# SCH_keeley_4_knob_compressor_2022-01-26.net
KiCad netlist of a schematic drawn in EasyEDA
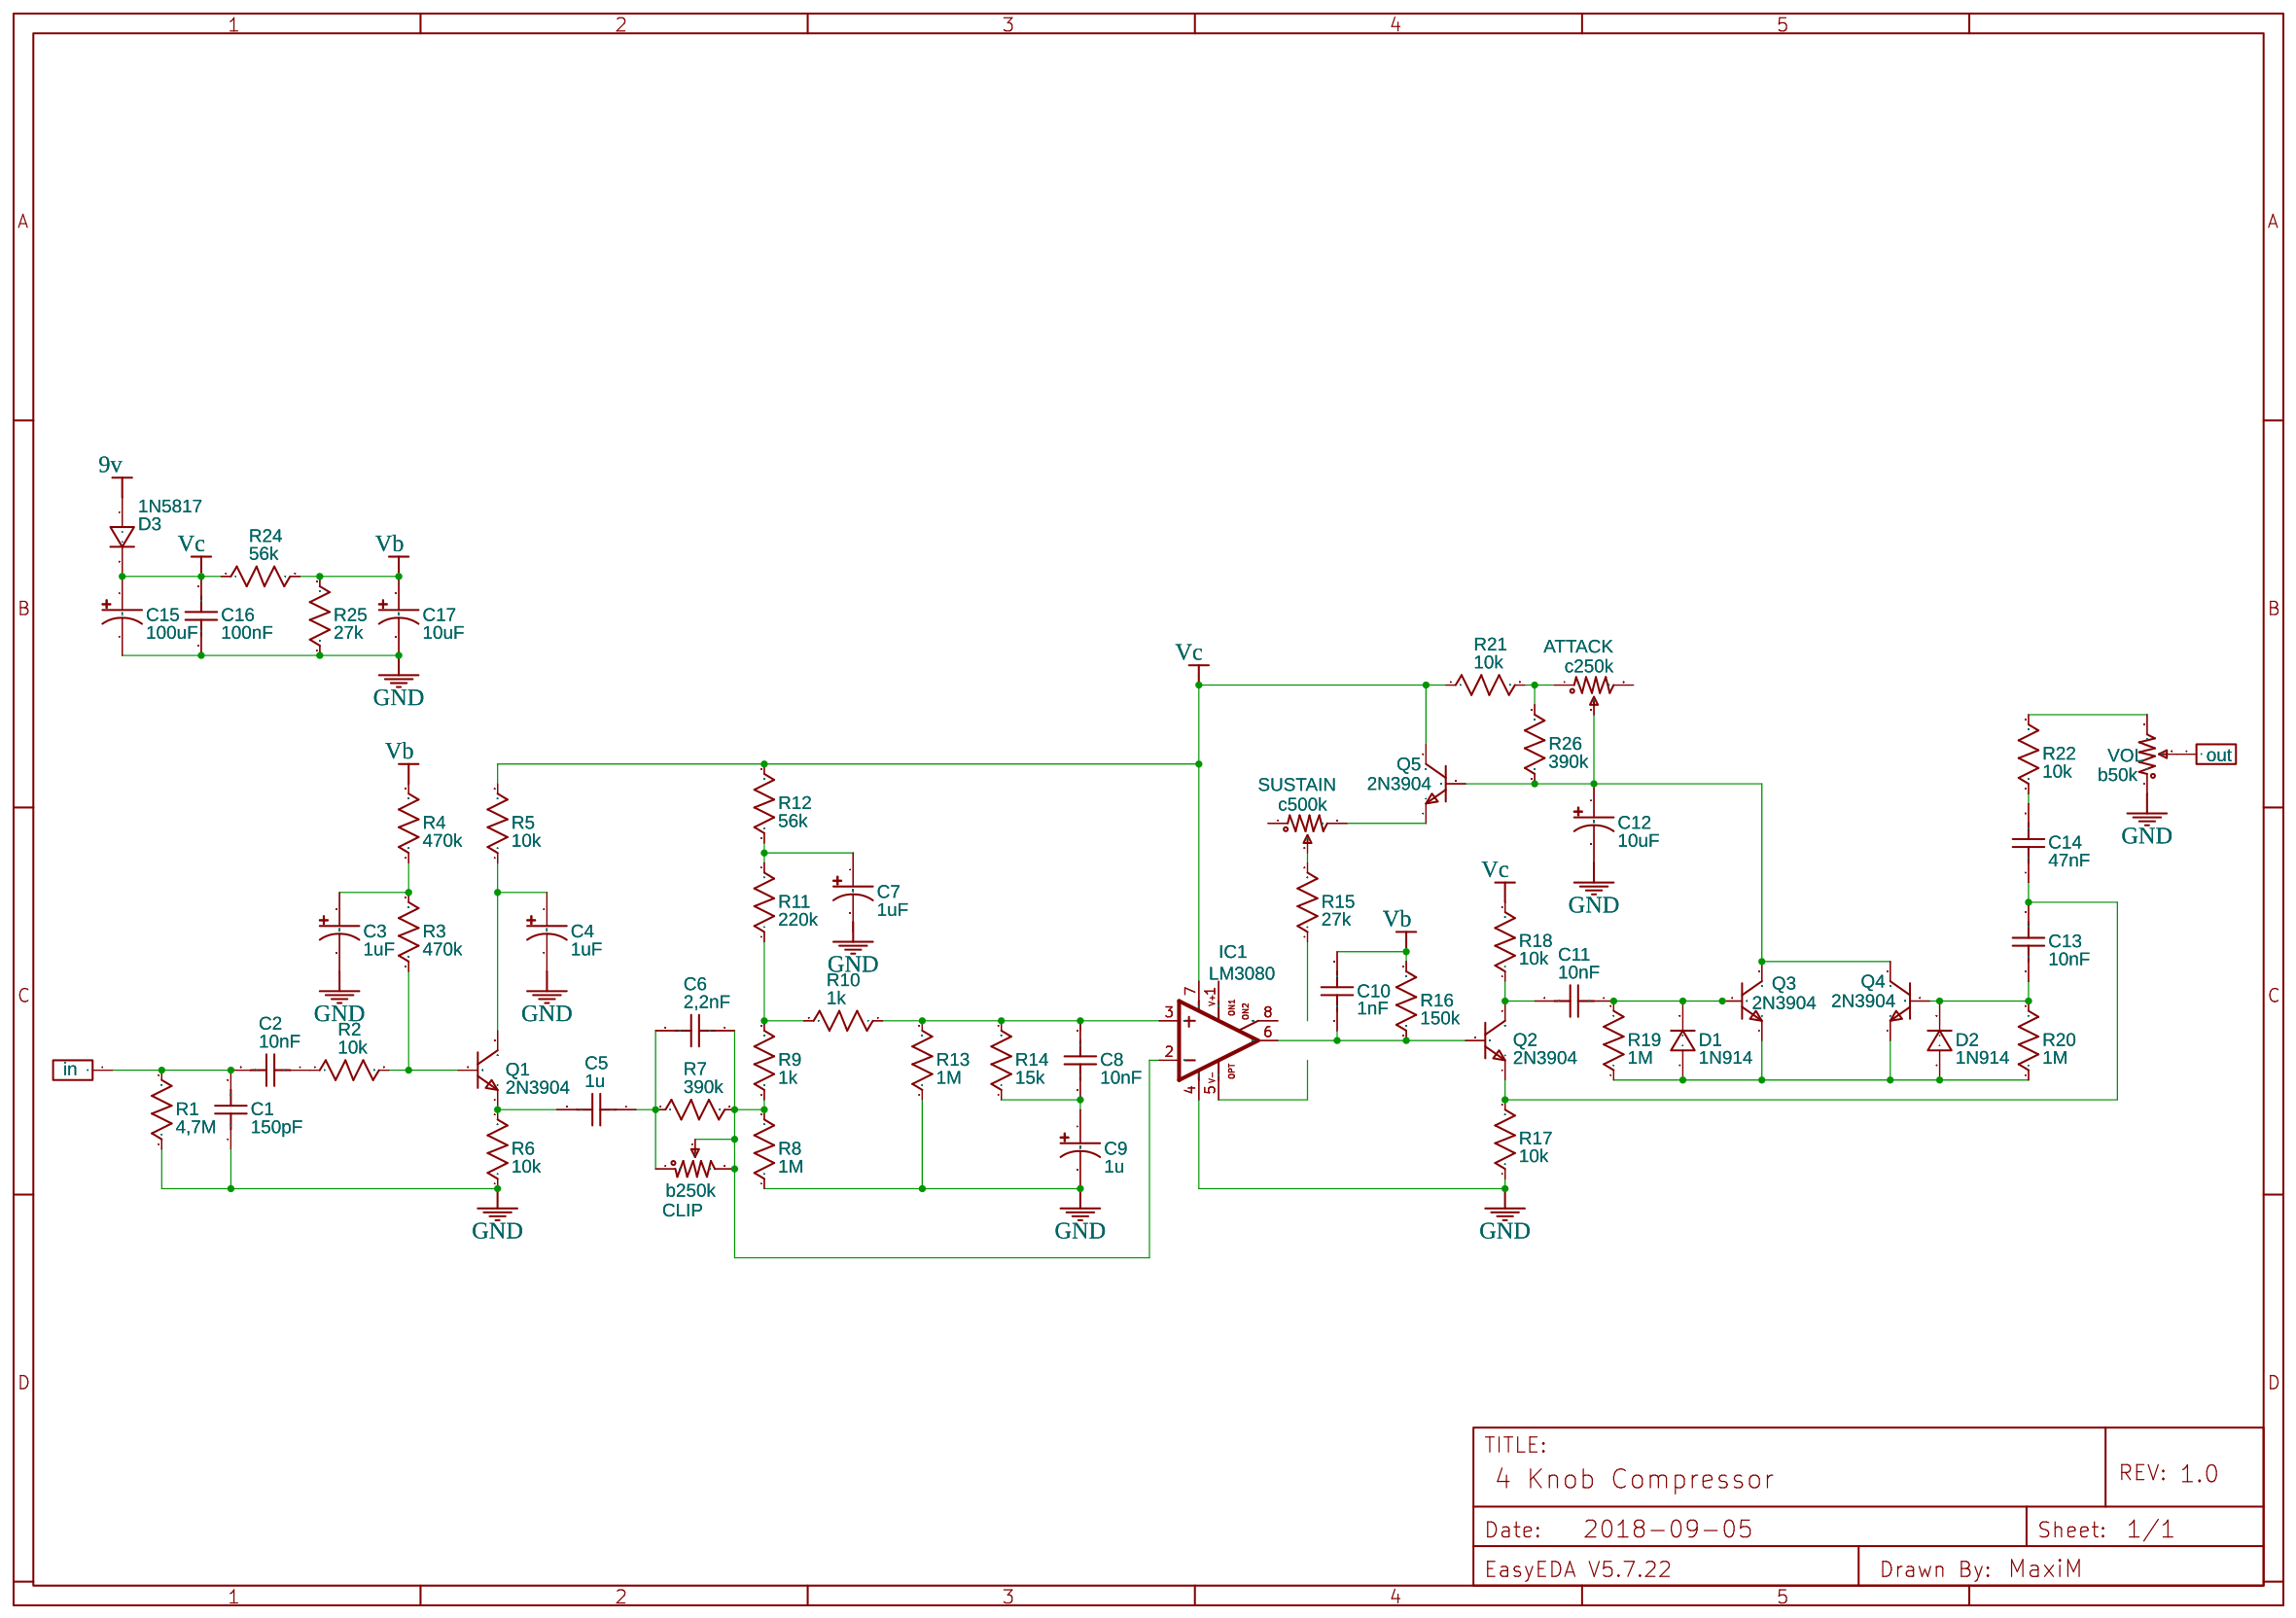
[diagram p0: schematic sheet]

(export (version "E")
  (design (tool "Eeschema 10.0.6"))
  (components
    (comp (ref "ATTACK")
      (value "c250k")
      (fields
        (field (name "BOM_Manufacturer Part") "3386P-1-101LF")
        (field (name "BOM_Supplier Part") "C125022")
      )
      (libsource (lib "") (part "3386P-1-101LF_US_2"))
    )
    (comp (ref "C1")
      (value "150pF")
      (fields (field (name "BOM_Manufacturer Part") "?"))
      (libsource (lib "") (part "Cap_RAD-0.1_US_1"))
    )
    (comp (ref "C2")
      (value "10nF")
      (fields (field (name "BOM_Manufacturer Part") "?"))
      (libsource (lib "") (part "Cap_RAD-0.1_US"))
    )
    (comp (ref "C3")
      (value "1uF")
      (fields (field (name "BOM_Manufacturer Part") "?"))
      (libsource (lib "") (part "Cap_Electrolytic(TH)_D3.0XF1.5_US_1"))
    )
    (comp (ref "C4")
      (value "1uF")
      (fields (field (name "BOM_Manufacturer Part") "?"))
      (libsource (lib "") (part "Cap_Electrolytic(TH)_D3.0XF1.5_US"))
    )
    (comp (ref "C5")
      (value "1u")
      (fields (field (name "BOM_Manufacturer Part") "?"))
      (libsource (lib "") (part "Cap_RAD-0.1_US"))
    )
    (comp (ref "C6")
      (value "2,2nF")
      (fields (field (name "BOM_Manufacturer Part") "?"))
      (libsource (lib "") (part "Cap_RAD-0.1_US"))
    )
    (comp (ref "C7")
      (value "1uF")
      (fields (field (name "BOM_Manufacturer Part") "?"))
      (libsource (lib "") (part "Cap_Electrolytic(TH)_D3.0XF1.5_US"))
    )
    (comp (ref "C8")
      (value "10nF")
      (fields (field (name "BOM_Manufacturer Part") "?"))
      (libsource (lib "") (part "Cap_RAD-0.1_US_1"))
    )
    (comp (ref "C9")
      (value "1u")
      (fields (field (name "BOM_Manufacturer Part") "?"))
      (libsource (lib "") (part "Cap_Electrolytic(TH)_D3.0XF1.5_US"))
    )
    (comp (ref "C10")
      (value "1nF")
      (fields (field (name "BOM_Manufacturer Part") "?"))
      (libsource (lib "") (part "Cap_RAD-0.1_US_1"))
    )
    (comp (ref "C11")
      (value "10nF")
      (fields (field (name "BOM_Manufacturer Part") "?"))
      (libsource (lib "") (part "Cap_RAD-0.1_US"))
    )
    (comp (ref "C12")
      (value "10uF")
      (fields (field (name "BOM_Manufacturer Part") "?"))
      (libsource (lib "") (part "Cap_Electrolytic(TH)_D3.0XF1.5_US"))
    )
    (comp (ref "C13")
      (value "10nF")
      (fields (field (name "BOM_Manufacturer Part") "?"))
      (libsource (lib "") (part "Cap_RAD-0.1_US_1"))
    )
    (comp (ref "C14")
      (value "47nF")
      (fields (field (name "BOM_Manufacturer Part") "?"))
      (libsource (lib "") (part "Cap_RAD-0.1_US_1"))
    )
    (comp (ref "C15")
      (value "100uF")
      (fields (field (name "BOM_Manufacturer Part") "?"))
      (libsource (lib "") (part "Cap_Electrolytic(TH)_D3.0XF1.5_US"))
    )
    (comp (ref "C16")
      (value "100nF")
      (fields (field (name "BOM_Manufacturer Part") "?"))
      (libsource (lib "") (part "Cap_RAD-0.1_US_1"))
    )
    (comp (ref "C17")
      (value "10uF")
      (fields (field (name "BOM_Manufacturer Part") "?"))
      (libsource (lib "") (part "Cap_Electrolytic(TH)_D3.0XF1.5_US_1"))
    )
    (comp (ref "CLIP")
      (value "b250k")
      (fields
        (field (name "BOM_Manufacturer Part") "3386P-1-101LF")
        (field (name "BOM_Supplier Part") "C125022")
      )
      (libsource (lib "") (part "3386P-1-101LF_US_3"))
    )
    (comp (ref "D1")
      (value "1N914")
      (fields (field (name "BOM_Manufacturer Part") "1N4448") (field (name "BOM_Supplier Part") "C54037"))
      (libsource (lib "") (part "Unknown_845_520"))
    )
    (comp (ref "D2")
      (value "1N914")
      (fields (field (name "BOM_Manufacturer Part") "1N4448") (field (name "BOM_Supplier Part") "C54037"))
      (libsource (lib "") (part "Unknown_975_520"))
    )
    (comp (ref "D3")
      (value "1N5817")
      (fields (field (name "BOM_Manufacturer Part") "1N4448") (field (name "BOM_Supplier Part") "C54037"))
      (libsource (lib "") (part "Unknown_55_265"))
    )
    (comp (ref "IC1")
      (value "LM3080")
      (fields (field (name "BOM_Manufacturer Part") "?"))
      (libsource (lib "") (part "Unknown_610_520"))
    )
    (comp (ref "P1")
      (value "in")
      (fields
        (field (name "BOM_Manufacturer Part") "Header-Male-2.54_1x1")
        (field (name "BOM_Supplier Part") "C81276")
      )
      (libsource (lib "") (part "Unknown_35_535"))
    )
    (comp (ref "P2")
      (value "out")
      (fields
        (field (name "BOM_Manufacturer Part") "Header-Male-2.54_1x1")
        (field (name "BOM_Supplier Part") "C81276")
      )
      (libsource (lib "") (part "Unknown_1110_375"))
    )
    (comp (ref "Q1")
      (value "2N3904")
      (fields (field (name "BOM_Supplier Part") "C118538"))
      (libsource (lib "") (part "Unknown_235_535"))
    )
    (comp (ref "Q2")
      (value "2N3904")
      (fields (field (name "BOM_Supplier Part") "C118538"))
      (libsource (lib "") (part "Unknown_745_520"))
    )
    (comp (ref "Q3")
      (value "2N3904")
      (fields (field (name "BOM_Supplier Part") "C118538"))
      (libsource (lib "") (part "Unknown_875_500"))
    )
    (comp (ref "Q4")
      (value "2N3904")
      (fields (field (name "BOM_Supplier Part") "C118538"))
      (libsource (lib "") (part "Unknown_960_500"))
    )
    (comp (ref "Q5")
      (value "2N3904")
      (fields (field (name "BOM_Supplier Part") "C118538"))
      (libsource (lib "") (part "Unknown_725_390"))
    )
    (comp (ref "R1")
      (value "4,7M")
      (fields (field (name "BOM_Manufacturer Part") "?"))
      (libsource (lib "") (part "Res_AXIAL-0.4(1/4W)_US"))
    )
    (comp (ref "R2")
      (value "10k")
      (fields (field (name "BOM_Manufacturer Part") "?"))
      (libsource (lib "") (part "Res_AXIAL-0.4(1/4W)_US_1"))
    )
    (comp (ref "R3")
      (value "470k")
      (fields (field (name "BOM_Manufacturer Part") "?"))
      (libsource (lib "") (part "Res_AXIAL-0.4(1/4W)_US"))
    )
    (comp (ref "R4")
      (value "470k")
      (fields (field (name "BOM_Manufacturer Part") "?"))
      (libsource (lib "") (part "Res_AXIAL-0.4(1/4W)_US"))
    )
    (comp (ref "R5")
      (value "10k")
      (fields (field (name "BOM_Manufacturer Part") "?"))
      (libsource (lib "") (part "Res_AXIAL-0.4(1/4W)_US"))
    )
    (comp (ref "R6")
      (value "10k")
      (fields (field (name "BOM_Manufacturer Part") "?"))
      (libsource (lib "") (part "Res_AXIAL-0.4(1/4W)_US"))
    )
    (comp (ref "R7")
      (value "390k")
      (fields (field (name "BOM_Manufacturer Part") "?"))
      (libsource (lib "") (part "Res_AXIAL-0.4(1/4W)_US_1"))
    )
    (comp (ref "R8")
      (value "1M")
      (fields (field (name "BOM_Manufacturer Part") "?"))
      (libsource (lib "") (part "Res_AXIAL-0.4(1/4W)_US"))
    )
    (comp (ref "R9")
      (value "1k")
      (fields (field (name "BOM_Manufacturer Part") "?"))
      (libsource (lib "") (part "Res_AXIAL-0.4(1/4W)_US"))
    )
    (comp (ref "R10")
      (value "1k")
      (fields (field (name "BOM_Manufacturer Part") "?"))
      (libsource (lib "") (part "Res_AXIAL-0.4(1/4W)_US_2"))
    )
    (comp (ref "R11")
      (value "220k")
      (fields (field (name "BOM_Manufacturer Part") "?"))
      (libsource (lib "") (part "Res_AXIAL-0.4(1/4W)_US"))
    )
    (comp (ref "R12")
      (value "56k")
      (fields (field (name "BOM_Manufacturer Part") "?"))
      (libsource (lib "") (part "Res_AXIAL-0.4(1/4W)_US"))
    )
    (comp (ref "R13")
      (value "1M")
      (fields (field (name "BOM_Manufacturer Part") "?"))
      (libsource (lib "") (part "Res_AXIAL-0.4(1/4W)_US"))
    )
    (comp (ref "R14")
      (value "15k")
      (fields (field (name "BOM_Manufacturer Part") "?"))
      (libsource (lib "") (part "Res_AXIAL-0.4(1/4W)_US"))
    )
    (comp (ref "R15")
      (value "27k")
      (fields (field (name "BOM_Manufacturer Part") "?"))
      (libsource (lib "") (part "Res_AXIAL-0.4(1/4W)_US"))
    )
    (comp (ref "R16")
      (value "150k")
      (fields (field (name "BOM_Manufacturer Part") "?"))
      (libsource (lib "") (part "Res_AXIAL-0.4(1/4W)_US"))
    )
    (comp (ref "R17")
      (value "10k")
      (fields (field (name "BOM_Manufacturer Part") "?"))
      (libsource (lib "") (part "Res_AXIAL-0.4(1/4W)_US"))
    )
    (comp (ref "R18")
      (value "10k")
      (fields (field (name "BOM_Manufacturer Part") "?"))
      (libsource (lib "") (part "Res_AXIAL-0.4(1/4W)_US"))
    )
    (comp (ref "R19")
      (value "1M")
      (fields (field (name "BOM_Manufacturer Part") "?"))
      (libsource (lib "") (part "Res_AXIAL-0.4(1/4W)_US"))
    )
    (comp (ref "R20")
      (value "1M")
      (fields (field (name "BOM_Manufacturer Part") "?"))
      (libsource (lib "") (part "Res_AXIAL-0.4(1/4W)_US"))
    )
    (comp (ref "R21")
      (value "10k")
      (fields (field (name "BOM_Manufacturer Part") "?"))
      (libsource (lib "") (part "Res_AXIAL-0.4(1/4W)_US_1"))
    )
    (comp (ref "R22")
      (value "10k")
      (fields (field (name "BOM_Manufacturer Part") "?"))
      (libsource (lib "") (part "Res_AXIAL-0.4(1/4W)_US"))
    )
    (comp (ref "R24")
      (value "56k")
      (fields (field (name "BOM_Manufacturer Part") "?"))
      (libsource (lib "") (part "Res_AXIAL-0.4(1/4W)_US_1"))
    )
    (comp (ref "R25")
      (value "27k")
      (fields (field (name "BOM_Manufacturer Part") "?"))
      (libsource (lib "") (part "Res_AXIAL-0.4(1/4W)_US"))
    )
    (comp (ref "R26")
      (value "390k")
      (fields (field (name "BOM_Manufacturer Part") "?"))
      (libsource (lib "") (part "Res_AXIAL-0.4(1/4W)_US"))
    )
    (comp (ref "SUSTAIN")
      (value "c500k")
      (fields
        (field (name "BOM_Manufacturer Part") "3386P-1-101LF")
        (field (name "BOM_Supplier Part") "C125022")
      )
      (libsource (lib "") (part "3386P-1-101LF_US"))
    )
    (comp (ref "VOL")
      (value "b50k")
      (fields
        (field (name "BOM_Manufacturer Part") "3386P-1-101LF")
        (field (name "BOM_Supplier Part") "C125022")
      )
      (libsource (lib "") (part "3386P-1-101LF_US_1"))
    )
  )
  (nets
    (net (code "1") (name "9v") (class "Default")
      (node (ref "D3") (pin "1") (pinfunction "A_1") (pintype "unspecified"))
    )
    (net (code "2") (name "GND") (class "Default")
      (node (ref "C1") (pin "1") (pinfunction "1_1") (pintype "unspecified"))
      (node (ref "C12") (pin "2") (pinfunction "2_2") (pintype "unspecified"))
      (node (ref "C15") (pin "2") (pinfunction "2_2") (pintype "unspecified"))
      (node (ref "C16") (pin "1") (pinfunction "1_1") (pintype "unspecified"))
      (node (ref "C17") (pin "2") (pinfunction "2_2") (pintype "unspecified"))
      (node (ref "C3") (pin "2") (pinfunction "2_2") (pintype "unspecified"))
      (node (ref "C4") (pin "2") (pinfunction "2_2") (pintype "unspecified"))
      (node (ref "C9") (pin "2") (pinfunction "2_2") (pintype "unspecified"))
      (node (ref "IC1") (pin "4") (pinfunction "V-_4") (pintype "passive"))
      (node (ref "R1") (pin "1") (pinfunction "1_1") (pintype "unspecified"))
      (node (ref "R13") (pin "1") (pinfunction "1_1") (pintype "unspecified"))
      (node (ref "R17") (pin "1") (pinfunction "1_1") (pintype "unspecified"))
      (node (ref "R25") (pin "1") (pinfunction "1_1") (pintype "unspecified"))
      (node (ref "R6") (pin "1") (pinfunction "1_1") (pintype "unspecified"))
      (node (ref "R8") (pin "1") (pinfunction "1_1") (pintype "unspecified"))
      (node (ref "VOL") (pin "1") (pinfunction "1_1") (pintype "unspecified"))
    )
    (net (code "3") (name "Net-(ATTACK-Pad1)") (class "Default")
      (node (ref "ATTACK") (pin "1") (pinfunction "1_1") (pintype "unspecified"))
      (node (ref "R21") (pin "2") (pinfunction "2_2") (pintype "unspecified"))
      (node (ref "R26") (pin "2") (pinfunction "2_2") (pintype "unspecified"))
    )
    (net (code "4") (name "Net-(C1-Pad2)") (class "Default")
      (node (ref "C1") (pin "2") (pinfunction "2_2") (pintype "unspecified"))
      (node (ref "C2") (pin "2") (pinfunction "2_2") (pintype "unspecified"))
      (node (ref "P1") (pin "1") (pinfunction "1_1") (pintype "input"))
      (node (ref "R1") (pin "2") (pinfunction "2_2") (pintype "unspecified"))
    )
    (net (code "5") (name "Net-(C2-Pad1)") (class "Default")
      (node (ref "C2") (pin "1") (pinfunction "1_1") (pintype "unspecified"))
      (node (ref "R2") (pin "1") (pinfunction "1_1") (pintype "unspecified"))
    )
    (net (code "6") (name "Net-(C3-Pad1)") (class "Default")
      (node (ref "C3") (pin "1") (pinfunction "1_1") (pintype "unspecified"))
      (node (ref "R3") (pin "2") (pinfunction "2_2") (pintype "unspecified"))
      (node (ref "R4") (pin "1") (pinfunction "1_1") (pintype "unspecified"))
    )
    (net (code "7") (name "Net-(C5-Pad1)") (class "Default")
      (node (ref "C5") (pin "1") (pinfunction "1_1") (pintype "unspecified"))
      (node (ref "C6") (pin "2") (pinfunction "2_2") (pintype "unspecified"))
      (node (ref "CLIP") (pin "1") (pinfunction "1_1") (pintype "unspecified"))
      (node (ref "R7") (pin "1") (pinfunction "1_1") (pintype "unspecified"))
    )
    (net (code "8") (name "Net-(C7-Pad1)") (class "Default")
      (node (ref "C7") (pin "1") (pinfunction "1_1") (pintype "unspecified"))
      (node (ref "R11") (pin "2") (pinfunction "2_2") (pintype "unspecified"))
      (node (ref "R12") (pin "1") (pinfunction "1_1") (pintype "unspecified"))
    )
    (net (code "9") (name "Net-(C8-Pad1)") (class "Default")
      (node (ref "C8") (pin "1") (pinfunction "1_1") (pintype "unspecified"))
      (node (ref "C9") (pin "1") (pinfunction "1_1") (pintype "unspecified"))
      (node (ref "R14") (pin "1") (pinfunction "1_1") (pintype "unspecified"))
    )
    (net (code "10") (name "Net-(C14-Pad2)") (class "Default")
      (node (ref "C14") (pin "2") (pinfunction "2_2") (pintype "unspecified"))
      (node (ref "R22") (pin "1") (pinfunction "1_1") (pintype "unspecified"))
    )
    (net (code "11") (name "Net-(D1-A)") (class "Default")
      (node (ref "D1") (pin "1") (pinfunction "A_1") (pintype "unspecified"))
      (node (ref "D2") (pin "1") (pinfunction "A_1") (pintype "unspecified"))
      (node (ref "Q3") (pin "1") (pinfunction "E_1") (pintype "unspecified"))
      (node (ref "Q4") (pin "1") (pinfunction "E_1") (pintype "unspecified"))
      (node (ref "R19") (pin "1") (pinfunction "1_1") (pintype "unspecified"))
      (node (ref "R20") (pin "1") (pinfunction "1_1") (pintype "unspecified"))
    )
    (net (code "12") (name "Net-(D1-K)") (class "Default")
      (node (ref "C11") (pin "1") (pinfunction "1_1") (pintype "unspecified"))
      (node (ref "D1") (pin "2") (pinfunction "K_2") (pintype "unspecified"))
      (node (ref "Q3") (pin "2") (pinfunction "B_2") (pintype "unspecified"))
      (node (ref "R19") (pin "2") (pinfunction "2_2") (pintype "unspecified"))
    )
    (net (code "13") (name "Net-(D2-K)") (class "Default")
      (node (ref "C13") (pin "1") (pinfunction "1_1") (pintype "unspecified"))
      (node (ref "D2") (pin "2") (pinfunction "K_2") (pintype "unspecified"))
      (node (ref "Q4") (pin "2") (pinfunction "B_2") (pintype "unspecified"))
      (node (ref "R20") (pin "2") (pinfunction "2_2") (pintype "unspecified"))
    )
    (net (code "14") (name "Net-(IC1-+IN)") (class "Default")
      (node (ref "C8") (pin "2") (pinfunction "2_2") (pintype "unspecified"))
      (node (ref "IC1") (pin "3") (pinfunction "+IN_3") (pintype "input"))
      (node (ref "R10") (pin "1") (pinfunction "1_1") (pintype "unspecified"))
      (node (ref "R13") (pin "2") (pinfunction "2_2") (pintype "unspecified"))
      (node (ref "R14") (pin "2") (pinfunction "2_2") (pintype "unspecified"))
    )
    (net (code "15") (name "Net-(IC1--IN)") (class "Default")
      (node (ref "C6") (pin "1") (pinfunction "1_1") (pintype "unspecified"))
      (node (ref "CLIP") (pin "2") (pinfunction "2_2") (pintype "unspecified"))
      (node (ref "CLIP") (pin "3") (pinfunction "3_3") (pintype "unspecified"))
      (node (ref "IC1") (pin "2") (pinfunction "-IN_2") (pintype "input"))
      (node (ref "R7") (pin "2") (pinfunction "2_2") (pintype "unspecified"))
      (node (ref "R8") (pin "2") (pinfunction "2_2") (pintype "unspecified"))
      (node (ref "R9") (pin "1") (pinfunction "1_1") (pintype "unspecified"))
    )
    (net (code "16") (name "Net-(IC1-OUT)") (class "Default")
      (node (ref "C10") (pin "1") (pinfunction "1_1") (pintype "unspecified"))
      (node (ref "IC1") (pin "6") (pinfunction "OUT_6") (pintype "output"))
      (node (ref "Q2") (pin "2") (pinfunction "B_2") (pintype "unspecified"))
      (node (ref "R16") (pin "1") (pinfunction "1_1") (pintype "unspecified"))
    )
    (net (code "17") (name "Net-(P2-Pad1)") (class "Default")
      (node (ref "P2") (pin "1") (pinfunction "1_1") (pintype "input"))
      (node (ref "VOL") (pin "2") (pinfunction "2_2") (pintype "unspecified"))
    )
    (net (code "18") (name "Net-(Q1-B)") (class "Default")
      (node (ref "Q1") (pin "2") (pinfunction "B_2") (pintype "unspecified"))
      (node (ref "R2") (pin "2") (pinfunction "2_2") (pintype "unspecified"))
      (node (ref "R3") (pin "1") (pinfunction "1_1") (pintype "unspecified"))
    )
    (net (code "19") (name "Net-(Q1-C)") (class "Default")
      (node (ref "C4") (pin "1") (pinfunction "1_1") (pintype "unspecified"))
      (node (ref "Q1") (pin "3") (pinfunction "C_3") (pintype "unspecified"))
      (node (ref "R5") (pin "1") (pinfunction "1_1") (pintype "unspecified"))
    )
    (net (code "20") (name "Net-(Q1-E)") (class "Default")
      (node (ref "C5") (pin "2") (pinfunction "2_2") (pintype "unspecified"))
      (node (ref "Q1") (pin "1") (pinfunction "E_1") (pintype "unspecified"))
      (node (ref "R6") (pin "2") (pinfunction "2_2") (pintype "unspecified"))
    )
    (net (code "21") (name "Net-(Q2-C)") (class "Default")
      (node (ref "C11") (pin "2") (pinfunction "2_2") (pintype "unspecified"))
      (node (ref "Q2") (pin "3") (pinfunction "C_3") (pintype "unspecified"))
      (node (ref "R18") (pin "1") (pinfunction "1_1") (pintype "unspecified"))
    )
    (net (code "22") (name "Net-(Q2-E)") (class "Default")
      (node (ref "C13") (pin "2") (pinfunction "2_2") (pintype "unspecified"))
      (node (ref "C14") (pin "1") (pinfunction "1_1") (pintype "unspecified"))
      (node (ref "Q2") (pin "1") (pinfunction "E_1") (pintype "unspecified"))
      (node (ref "R17") (pin "2") (pinfunction "2_2") (pintype "unspecified"))
    )
    (net (code "23") (name "Net-(Q3-C)") (class "Default")
      (node (ref "ATTACK") (pin "2") (pinfunction "2_2") (pintype "unspecified"))
      (node (ref "C12") (pin "1") (pinfunction "1_1") (pintype "unspecified"))
      (node (ref "Q3") (pin "3") (pinfunction "C_3") (pintype "unspecified"))
      (node (ref "Q4") (pin "3") (pinfunction "C_3") (pintype "unspecified"))
      (node (ref "Q5") (pin "2") (pinfunction "B_2") (pintype "unspecified"))
      (node (ref "R26") (pin "1") (pinfunction "1_1") (pintype "unspecified"))
    )
    (net (code "24") (name "Net-(Q5-E)") (class "Default")
      (node (ref "Q5") (pin "1") (pinfunction "E_1") (pintype "unspecified"))
      (node (ref "SUSTAIN") (pin "3") (pinfunction "3_3") (pintype "unspecified"))
    )
    (net (code "25") (name "Net-(R10-Pad2)") (class "Default")
      (node (ref "R10") (pin "2") (pinfunction "2_2") (pintype "unspecified"))
      (node (ref "R11") (pin "1") (pinfunction "1_1") (pintype "unspecified"))
      (node (ref "R9") (pin "2") (pinfunction "2_2") (pintype "unspecified"))
    )
    (net (code "26") (name "Net-(R15-Pad2)") (class "Default")
      (node (ref "R15") (pin "2") (pinfunction "2_2") (pintype "unspecified"))
      (node (ref "SUSTAIN") (pin "2") (pinfunction "2_2") (pintype "unspecified"))
    )
    (net (code "27") (name "Net-(R22-Pad2)") (class "Default")
      (node (ref "R22") (pin "2") (pinfunction "2_2") (pintype "unspecified"))
      (node (ref "VOL") (pin "3") (pinfunction "3_3") (pintype "unspecified"))
    )
    (net (code "28") (name "Vb") (class "Default")
      (node (ref "C10") (pin "2") (pinfunction "2_2") (pintype "unspecified"))
      (node (ref "C17") (pin "1") (pinfunction "1_1") (pintype "unspecified"))
      (node (ref "R16") (pin "2") (pinfunction "2_2") (pintype "unspecified"))
      (node (ref "R24") (pin "2") (pinfunction "2_2") (pintype "unspecified"))
      (node (ref "R25") (pin "2") (pinfunction "2_2") (pintype "unspecified"))
      (node (ref "R4") (pin "2") (pinfunction "2_2") (pintype "unspecified"))
    )
    (net (code "29") (name "Vc") (class "Default")
      (node (ref "C15") (pin "1") (pinfunction "1_1") (pintype "unspecified"))
      (node (ref "C16") (pin "2") (pinfunction "2_2") (pintype "unspecified"))
      (node (ref "D3") (pin "2") (pinfunction "K_2") (pintype "unspecified"))
      (node (ref "IC1") (pin "7") (pinfunction "V+_7") (pintype "passive"))
      (node (ref "Q5") (pin "3") (pinfunction "C_3") (pintype "unspecified"))
      (node (ref "R12") (pin "2") (pinfunction "2_2") (pintype "unspecified"))
      (node (ref "R18") (pin "2") (pinfunction "2_2") (pintype "unspecified"))
      (node (ref "R21") (pin "1") (pinfunction "1_1") (pintype "unspecified"))
      (node (ref "R24") (pin "1") (pinfunction "1_1") (pintype "unspecified"))
      (node (ref "R5") (pin "2") (pinfunction "2_2") (pintype "unspecified"))
    )
    (net (code "30") (name "unconnected-(ATTACK-Pad3)") (class "Default")
      (node (ref "ATTACK") (pin "3") (pinfunction "3_3") (pintype "unspecified"))
    )
    (net (code "31") (name "unconnected-(C7-Pad2)") (class "Default")
      (node (ref "C7") (pin "2") (pinfunction "2_2") (pintype "unspecified"))
    )
    (net (code "32") (name "unconnected-(IC1-ON1-Pad1)") (class "Default")
      (node (ref "IC1") (pin "1") (pinfunction "ON1_1") (pintype "unspecified"))
    )
    (net (code "33") (name "unconnected-(IC1-ON2-Pad8)") (class "Default")
      (node (ref "IC1") (pin "8") (pinfunction "ON2_8") (pintype "unspecified"))
    )
    (net (code "34") (name "unconnected-(IC1-OPT-Pad5)") (class "Default")
      (node (ref "IC1") (pin "5") (pinfunction "OPT_5") (pintype "unspecified"))
    )
    (net (code "35") (name "unconnected-(R15-Pad1)") (class "Default")
      (node (ref "R15") (pin "1") (pinfunction "1_1") (pintype "unspecified"))
    )
    (net (code "36") (name "unconnected-(SUSTAIN-Pad1)") (class "Default")
      (node (ref "SUSTAIN") (pin "1") (pinfunction "1_1") (pintype "unspecified"))
    )
  )
)
